# FrontIrArray.net
KiCad netlist of a schematic drawn in Altium Designer
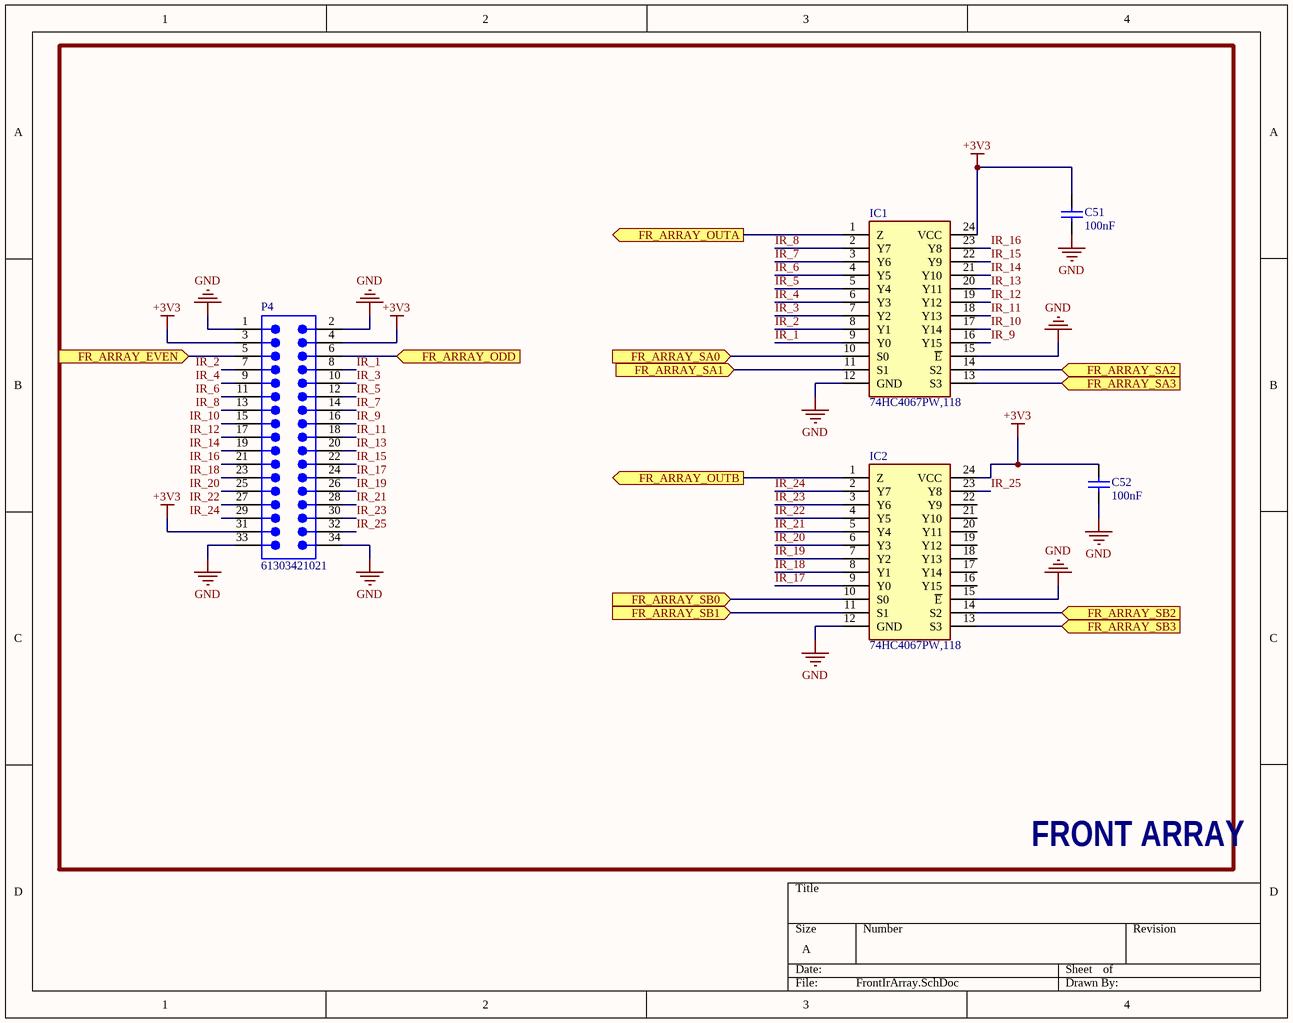
[diagram p0: FrontIrArray.SchDoc]

(export (version "E")
  (design (tool "Eeschema 10.0.6"))
  (components
    (comp (ref "C51")
      (value "CL05B104KO5NNNC")
      (footprint "CAPC1050X55X23ML05T13")
      (description "Chip Capacitor, 100 nF, +/- 10%, 16 V, -55 to 125 degC, 0402 (1005 Metric), RoHS, Tape and Reel")
      (fields (field (name "MANUFACTURER") "Samsung Electro-Mechanics") (field (name "CAPACITANCE") "100nF"))
      (libsource (lib "Altium Content Vault") (part "CAP-NP-2"))
    )
    (comp (ref "C52")
      (value "CL05B104KO5NNNC")
      (footprint "CAPC1050X55X23ML05T13")
      (description "Chip Capacitor, 100 nF, +/- 10%, 16 V, -55 to 125 degC, 0402 (1005 Metric), RoHS, Tape and Reel")
      (fields (field (name "MANUFACTURER") "Samsung Electro-Mechanics") (field (name "CAPACITANCE") "100nF"))
      (libsource (lib "Altium Content Vault") (part "CAP-NP-2"))
    )
    (comp (ref "IC1")
      (value "74HC4067PW,118")
      (footprint "SamacSys:SOP65P640X110-24N")
      (description "Integrated Circuit")
      (fields (field (name "MOUSER PART NUMBER") "771-74HC4067PW-T"))
      (libsource (lib "SamacSys") (part "74HC4067PW,118"))
    )
    (comp (ref "IC2")
      (value "74HC4067PW,118")
      (footprint "SamacSys:SOP65P640X110-24N")
      (description "Integrated Circuit")
      (fields (field (name "MOUSER PART NUMBER") "771-74HC4067PW-T"))
      (libsource (lib "SamacSys") (part "74HC4067PW,118"))
    )
    (comp (ref "P4")
      (value "61303421021")
      (footprint "61303421021")
      (libsource (lib "Altium Content Vault") (part "Header_Male_2R_34P"))
    )
  )
  (nets
    (net (code "1") (name "+3V3") (class "Default")
      (node (ref "C51") (pin "1") (pinfunction "1_1") (pintype "passive"))
      (node (ref "C52") (pin "1") (pinfunction "1_1") (pintype "passive"))
      (node (ref "IC1") (pin "24") (pinfunction "VCC_24") (pintype "passive"))
      (node (ref "IC2") (pin "24") (pinfunction "VCC_24") (pintype "passive"))
      (node (ref "P4") (pin "3") (pinfunction "3_3") (pintype "passive"))
      (node (ref "P4") (pin "31") (pinfunction "31_31") (pintype "passive"))
      (node (ref "P4") (pin "4") (pinfunction "4_4") (pintype "passive"))
    )
    (net (code "2") (name "/FR_ARRAY_EVEN") (class "Default")
      (node (ref "P4") (pin "5") (pinfunction "5_5") (pintype "passive"))
    )
    (net (code "3") (name "/FR_ARRAY_ODD") (class "Default")
      (node (ref "P4") (pin "6") (pinfunction "6_6") (pintype "passive"))
    )
    (net (code "4") (name "/FR_ARRAY_OUTA") (class "Default")
      (node (ref "IC1") (pin "1") (pinfunction "Z_1") (pintype "passive"))
    )
    (net (code "5") (name "/FR_ARRAY_OUTB") (class "Default")
      (node (ref "IC2") (pin "1") (pinfunction "Z_1") (pintype "passive"))
    )
    (net (code "6") (name "/FR_ARRAY_SA0") (class "Default")
      (node (ref "IC1") (pin "10") (pinfunction "S0_10") (pintype "passive"))
    )
    (net (code "7") (name "/FR_ARRAY_SA1") (class "Default")
      (node (ref "IC1") (pin "11") (pinfunction "S1_11") (pintype "passive"))
    )
    (net (code "8") (name "/FR_ARRAY_SA2") (class "Default")
      (node (ref "IC1") (pin "14") (pinfunction "S2_14") (pintype "passive"))
    )
    (net (code "9") (name "/FR_ARRAY_SA3") (class "Default")
      (node (ref "IC1") (pin "13") (pinfunction "S3_13") (pintype "passive"))
    )
    (net (code "10") (name "/FR_ARRAY_SB0") (class "Default")
      (node (ref "IC2") (pin "10") (pinfunction "S0_10") (pintype "passive"))
    )
    (net (code "11") (name "/FR_ARRAY_SB1") (class "Default")
      (node (ref "IC2") (pin "11") (pinfunction "S1_11") (pintype "passive"))
    )
    (net (code "12") (name "/FR_ARRAY_SB2") (class "Default")
      (node (ref "IC2") (pin "14") (pinfunction "S2_14") (pintype "passive"))
    )
    (net (code "13") (name "/FR_ARRAY_SB3") (class "Default")
      (node (ref "IC2") (pin "13") (pinfunction "S3_13") (pintype "passive"))
    )
    (net (code "14") (name "/IR_1") (class "Default")
      (node (ref "IC1") (pin "9") (pinfunction "Y0_9") (pintype "passive"))
      (node (ref "P4") (pin "8") (pinfunction "8_8") (pintype "passive"))
    )
    (net (code "15") (name "/IR_2") (class "Default")
      (node (ref "IC1") (pin "8") (pinfunction "Y1_8") (pintype "passive"))
      (node (ref "P4") (pin "7") (pinfunction "7_7") (pintype "passive"))
    )
    (net (code "16") (name "/IR_3") (class "Default")
      (node (ref "IC1") (pin "7") (pinfunction "Y2_7") (pintype "passive"))
      (node (ref "P4") (pin "10") (pinfunction "10_10") (pintype "passive"))
    )
    (net (code "17") (name "/IR_4") (class "Default")
      (node (ref "IC1") (pin "6") (pinfunction "Y3_6") (pintype "passive"))
      (node (ref "P4") (pin "9") (pinfunction "9_9") (pintype "passive"))
    )
    (net (code "18") (name "/IR_5") (class "Default")
      (node (ref "IC1") (pin "5") (pinfunction "Y4_5") (pintype "passive"))
      (node (ref "P4") (pin "12") (pinfunction "12_12") (pintype "passive"))
    )
    (net (code "19") (name "/IR_6") (class "Default")
      (node (ref "IC1") (pin "4") (pinfunction "Y5_4") (pintype "passive"))
      (node (ref "P4") (pin "11") (pinfunction "11_11") (pintype "passive"))
    )
    (net (code "20") (name "/IR_7") (class "Default")
      (node (ref "IC1") (pin "3") (pinfunction "Y6_3") (pintype "passive"))
      (node (ref "P4") (pin "14") (pinfunction "14_14") (pintype "passive"))
    )
    (net (code "21") (name "/IR_8") (class "Default")
      (node (ref "IC1") (pin "2") (pinfunction "Y7_2") (pintype "passive"))
      (node (ref "P4") (pin "13") (pinfunction "13_13") (pintype "passive"))
    )
    (net (code "22") (name "/IR_9") (class "Default")
      (node (ref "IC1") (pin "16") (pinfunction "Y15_16") (pintype "passive"))
      (node (ref "P4") (pin "16") (pinfunction "16_16") (pintype "passive"))
    )
    (net (code "23") (name "/IR_10") (class "Default")
      (node (ref "IC1") (pin "17") (pinfunction "Y14_17") (pintype "passive"))
      (node (ref "P4") (pin "15") (pinfunction "15_15") (pintype "passive"))
    )
    (net (code "24") (name "/IR_11") (class "Default")
      (node (ref "IC1") (pin "18") (pinfunction "Y13_18") (pintype "passive"))
      (node (ref "P4") (pin "18") (pinfunction "18_18") (pintype "passive"))
    )
    (net (code "25") (name "/IR_12") (class "Default")
      (node (ref "IC1") (pin "19") (pinfunction "Y12_19") (pintype "passive"))
      (node (ref "P4") (pin "17") (pinfunction "17_17") (pintype "passive"))
    )
    (net (code "26") (name "/IR_13") (class "Default")
      (node (ref "IC1") (pin "20") (pinfunction "Y11_20") (pintype "passive"))
      (node (ref "P4") (pin "20") (pinfunction "20_20") (pintype "passive"))
    )
    (net (code "27") (name "/IR_14") (class "Default")
      (node (ref "IC1") (pin "21") (pinfunction "Y10_21") (pintype "passive"))
      (node (ref "P4") (pin "19") (pinfunction "19_19") (pintype "passive"))
    )
    (net (code "28") (name "/IR_15") (class "Default")
      (node (ref "IC1") (pin "22") (pinfunction "Y9_22") (pintype "passive"))
      (node (ref "P4") (pin "22") (pinfunction "22_22") (pintype "passive"))
    )
    (net (code "29") (name "/IR_16") (class "Default")
      (node (ref "IC1") (pin "23") (pinfunction "Y8_23") (pintype "passive"))
      (node (ref "P4") (pin "21") (pinfunction "21_21") (pintype "passive"))
    )
    (net (code "30") (name "/IR_17") (class "Default")
      (node (ref "IC2") (pin "9") (pinfunction "Y0_9") (pintype "passive"))
      (node (ref "P4") (pin "24") (pinfunction "24_24") (pintype "passive"))
    )
    (net (code "31") (name "/IR_18") (class "Default")
      (node (ref "IC2") (pin "8") (pinfunction "Y1_8") (pintype "passive"))
      (node (ref "P4") (pin "23") (pinfunction "23_23") (pintype "passive"))
    )
    (net (code "32") (name "/IR_19") (class "Default")
      (node (ref "IC2") (pin "7") (pinfunction "Y2_7") (pintype "passive"))
      (node (ref "P4") (pin "26") (pinfunction "26_26") (pintype "passive"))
    )
    (net (code "33") (name "/IR_20") (class "Default")
      (node (ref "IC2") (pin "6") (pinfunction "Y3_6") (pintype "passive"))
      (node (ref "P4") (pin "25") (pinfunction "25_25") (pintype "passive"))
    )
    (net (code "34") (name "/IR_21") (class "Default")
      (node (ref "IC2") (pin "5") (pinfunction "Y4_5") (pintype "passive"))
      (node (ref "P4") (pin "28") (pinfunction "28_28") (pintype "passive"))
    )
    (net (code "35") (name "/IR_22") (class "Default")
      (node (ref "IC2") (pin "4") (pinfunction "Y5_4") (pintype "passive"))
      (node (ref "P4") (pin "27") (pinfunction "27_27") (pintype "passive"))
    )
    (net (code "36") (name "/IR_23") (class "Default")
      (node (ref "IC2") (pin "3") (pinfunction "Y6_3") (pintype "passive"))
      (node (ref "P4") (pin "30") (pinfunction "30_30") (pintype "passive"))
    )
    (net (code "37") (name "/IR_24") (class "Default")
      (node (ref "IC2") (pin "2") (pinfunction "Y7_2") (pintype "passive"))
      (node (ref "P4") (pin "29") (pinfunction "29_29") (pintype "passive"))
    )
    (net (code "38") (name "/IR_25") (class "Default")
      (node (ref "IC2") (pin "23") (pinfunction "Y8_23") (pintype "passive"))
      (node (ref "P4") (pin "32") (pinfunction "32_32") (pintype "passive"))
    )
    (net (code "39") (name "GND") (class "Default")
      (node (ref "C51") (pin "2") (pinfunction "2_2") (pintype "passive"))
      (node (ref "C52") (pin "2") (pinfunction "2_2") (pintype "passive"))
      (node (ref "IC1") (pin "12") (pinfunction "GND_12") (pintype "passive"))
      (node (ref "IC1") (pin "15") (pinfunction "~{E}_15") (pintype "passive"))
      (node (ref "IC2") (pin "12") (pinfunction "GND_12") (pintype "passive"))
      (node (ref "IC2") (pin "15") (pinfunction "~{E}_15") (pintype "passive"))
      (node (ref "P4") (pin "1") (pinfunction "1_1") (pintype "passive"))
      (node (ref "P4") (pin "2") (pinfunction "2_2") (pintype "passive"))
      (node (ref "P4") (pin "33") (pinfunction "33_33") (pintype "passive"))
      (node (ref "P4") (pin "34") (pinfunction "34_34") (pintype "passive"))
    )
    (net (code "40") (name "unconnected-(IC2-Y9-Pad22)") (class "Default")
      (node (ref "IC2") (pin "22") (pinfunction "Y9_22") (pintype "passive"))
    )
    (net (code "41") (name "unconnected-(IC2-Y10-Pad21)") (class "Default")
      (node (ref "IC2") (pin "21") (pinfunction "Y10_21") (pintype "passive"))
    )
    (net (code "42") (name "unconnected-(IC2-Y11-Pad20)") (class "Default")
      (node (ref "IC2") (pin "20") (pinfunction "Y11_20") (pintype "passive"))
    )
    (net (code "43") (name "unconnected-(IC2-Y12-Pad19)") (class "Default")
      (node (ref "IC2") (pin "19") (pinfunction "Y12_19") (pintype "passive"))
    )
    (net (code "44") (name "unconnected-(IC2-Y13-Pad18)") (class "Default")
      (node (ref "IC2") (pin "18") (pinfunction "Y13_18") (pintype "passive"))
    )
    (net (code "45") (name "unconnected-(IC2-Y14-Pad17)") (class "Default")
      (node (ref "IC2") (pin "17") (pinfunction "Y14_17") (pintype "passive"))
    )
    (net (code "46") (name "unconnected-(IC2-Y15-Pad16)") (class "Default")
      (node (ref "IC2") (pin "16") (pinfunction "Y15_16") (pintype "passive"))
    )
  )
)
